# 150110_AriloTX_REV2_3_0_868MHZ_CORRECT_T.net
KiCad netlist of a schematic drawn in EAGLE
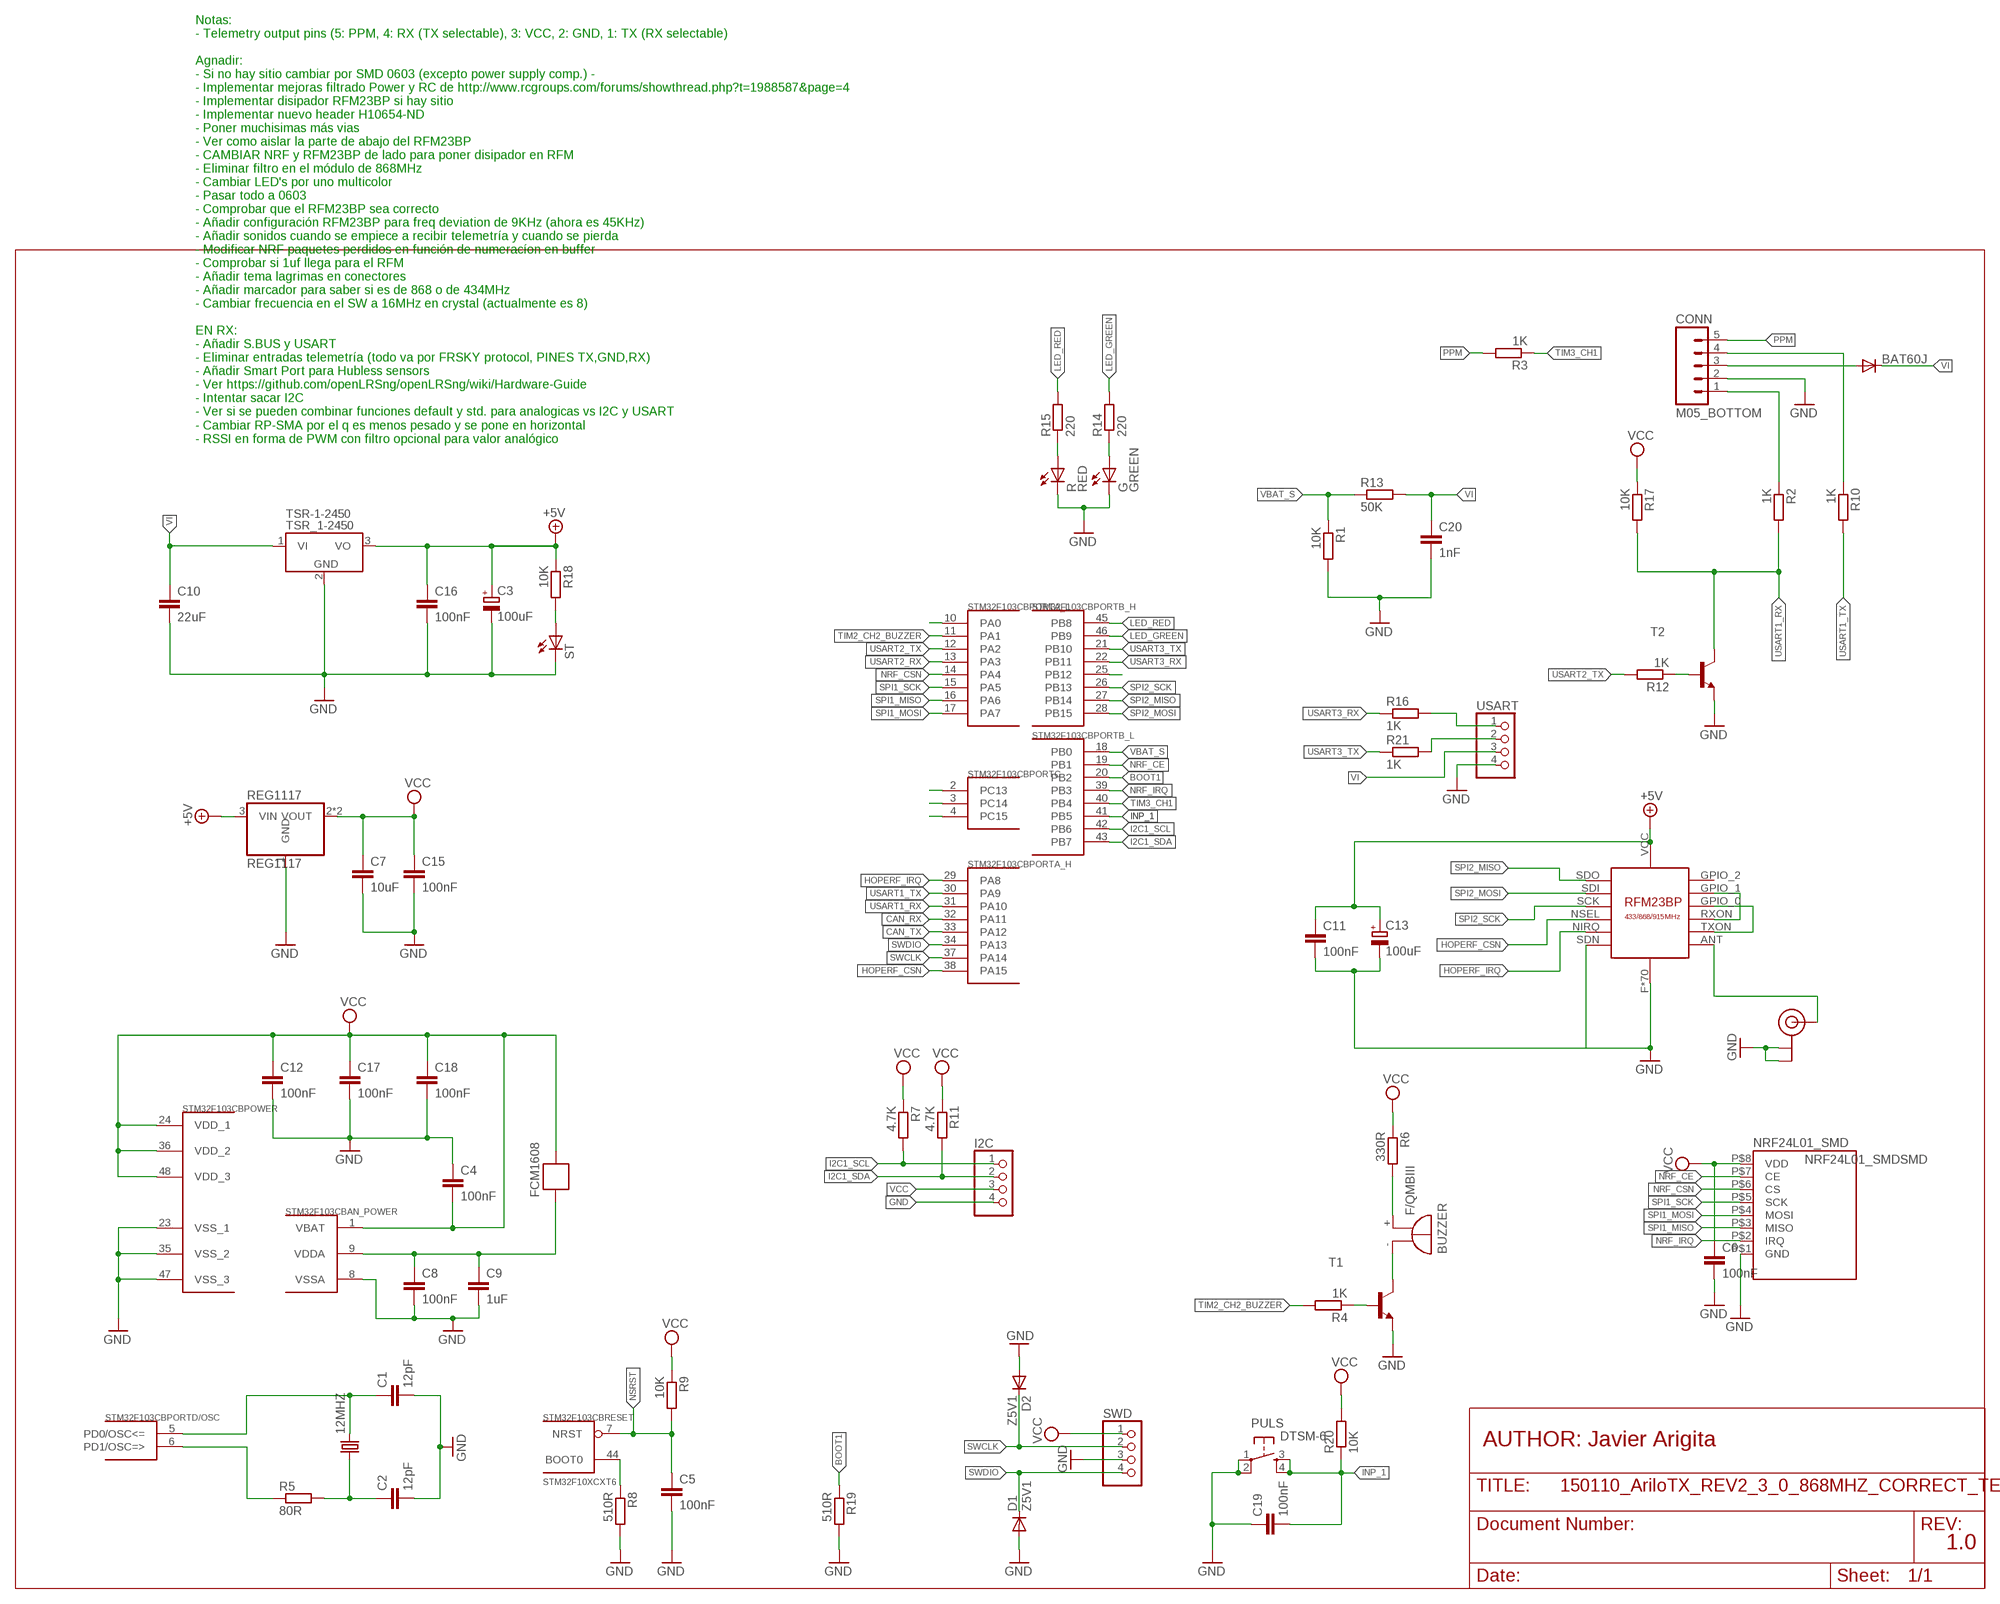
[diagram p0: schematic, sheet 1]

(export (version "E")
  (design (tool "Eeschema 10.0.6"))
  (components
    (comp (ref "12MHZ")
      (value "CRYSTAL5X3")
      (footprint "eagle-import:CRYSTAL-SMD-5X3")
      (libsource (lib "eagle-import") (part "CRYSTAL5X3"))
    )
    (comp (ref "BAT60J")
      (value "DIODE-SOD323-R")
      (footprint "eagle-import:SOD323-R")
      (libsource (lib "eagle-import") (part "DIODE-SOD323-R"))
    )
    (comp (ref "BUZZER")
      (value "F/QMBIII")
      (footprint "eagle-import:F_QMBIII")
      (libsource (lib "eagle-import") (part "F/QMBIII"))
    )
    (comp (ref "C1")
      (value "12pF")
      (footprint "eagle-import:C0603")
      (libsource (lib "eagle-import") (part "C-EUC0603"))
    )
    (comp (ref "C2")
      (value "12pF")
      (footprint "eagle-import:C0603")
      (libsource (lib "eagle-import") (part "C-EUC0603"))
    )
    (comp (ref "C3")
      (value "100uF")
      (footprint "eagle-import:SMC_B")
      (libsource (lib "eagle-import") (part "CPOL-EUSMCB"))
    )
    (comp (ref "C4")
      (value "100nF")
      (footprint "eagle-import:C0603")
      (libsource (lib "eagle-import") (part "C-EUC0603"))
    )
    (comp (ref "C5")
      (value "100nF")
      (footprint "eagle-import:C0603")
      (libsource (lib "eagle-import") (part "C-EUC0603"))
    )
    (comp (ref "C6")
      (value "100nF")
      (footprint "eagle-import:C0603")
      (libsource (lib "eagle-import") (part "C-EUC0603"))
    )
    (comp (ref "C7")
      (value "10uF")
      (footprint "eagle-import:C0805")
      (libsource (lib "eagle-import") (part "C-EUC0805"))
    )
    (comp (ref "C8")
      (value "100nF")
      (footprint "eagle-import:C0603")
      (libsource (lib "eagle-import") (part "C-EUC0603"))
    )
    (comp (ref "C9")
      (value "1uF")
      (footprint "eagle-import:C0603")
      (libsource (lib "eagle-import") (part "C-EUC0603"))
    )
    (comp (ref "C10")
      (value "22uF")
      (footprint "eagle-import:C3216")
      (libsource (lib "eagle-import") (part "resistor_C-EUC3216"))
    )
    (comp (ref "C11")
      (value "100nF")
      (footprint "eagle-import:C0603")
      (libsource (lib "eagle-import") (part "C-EUC0603"))
    )
    (comp (ref "C12")
      (value "100nF")
      (footprint "eagle-import:C0603")
      (libsource (lib "eagle-import") (part "C-EUC0603"))
    )
    (comp (ref "C13")
      (value "100uF")
      (footprint "eagle-import:SMC_B")
      (libsource (lib "eagle-import") (part "CPOL-EUSMCB"))
    )
    (comp (ref "C15")
      (value "100nF")
      (footprint "eagle-import:C0603")
      (libsource (lib "eagle-import") (part "C-EUC0603"))
    )
    (comp (ref "C16")
      (value "100nF")
      (footprint "eagle-import:C0603")
      (libsource (lib "eagle-import") (part "C-EUC0603"))
    )
    (comp (ref "C17")
      (value "100nF")
      (footprint "eagle-import:C0603")
      (libsource (lib "eagle-import") (part "C-EUC0603"))
    )
    (comp (ref "C18")
      (value "100nF")
      (footprint "eagle-import:C0603")
      (libsource (lib "eagle-import") (part "C-EUC0603"))
    )
    (comp (ref "C19")
      (value "100nF")
      (footprint "eagle-import:C0603")
      (libsource (lib "eagle-import") (part "C-EUC0603"))
    )
    (comp (ref "C20")
      (value "1nF")
      (footprint "eagle-import:C0603")
      (libsource (lib "eagle-import") (part "C-EUC0603"))
    )
    (comp (ref "CONN")
      (value "M05_BOTTOM")
      (footprint "eagle-import:M05_BOTTOM")
      (libsource (lib "eagle-import") (part "M05_BOTTOM"))
    )
    (comp (ref "D1")
      (value "Z5V1")
      (footprint "eagle-import:SOD323-R")
      (libsource (lib "eagle-import") (part "DIODE-SOD323-R"))
    )
    (comp (ref "D2")
      (value "Z5V1")
      (footprint "eagle-import:SOD323-R")
      (libsource (lib "eagle-import") (part "DIODE-SOD323-R"))
    )
    (comp (ref "FCM1608")
      (value "FERRITE-BEAD")
      (footprint "eagle-import:R0603")
      (libsource (lib "eagle-import") (part "FERRITE-BEAD"))
    )
    (comp (ref "G")
      (value "GREEN")
      (footprint "eagle-import:CHIP-LED0603")
      (libsource (lib "eagle-import") (part "LEDCHIP-LED0603"))
    )
    (comp (ref "I2C")
      (value "PINHD-1X4")
      (footprint "eagle-import:1X04")
      (libsource (lib "eagle-import") (part "PINHD-1X4"))
    )
    (comp (ref "NRF24L01_SMD")
      (value "NRF24L01_SMDSMD")
      (footprint "eagle-import:NRF24L01_SMD")
      (libsource (lib "eagle-import") (part "NRF24L01_SMDSMD"))
    )
    (comp (ref "PULS")
      (value "DTSM-6")
      (footprint "eagle-import:DTSM-6")
      (libsource (lib "eagle-import") (part "DTSM-6"))
    )
    (comp (ref "R")
      (value "RED")
      (footprint "eagle-import:CHIP-LED0603")
      (libsource (lib "eagle-import") (part "LEDCHIP-LED0603"))
    )
    (comp (ref "R1")
      (value "10K")
      (footprint "eagle-import:R0603")
      (libsource (lib "eagle-import") (part "R-EU_R0603"))
    )
    (comp (ref "R2")
      (value "1K")
      (footprint "eagle-import:R0603")
      (libsource (lib "eagle-import") (part "R-EU_R0603"))
    )
    (comp (ref "R3")
      (value "1K")
      (footprint "eagle-import:R0603")
      (libsource (lib "eagle-import") (part "R-EU_R0603"))
    )
    (comp (ref "R4")
      (value "1K")
      (footprint "eagle-import:R0603")
      (libsource (lib "eagle-import") (part "R-EU_R0603"))
    )
    (comp (ref "R5")
      (value "80R")
      (footprint "eagle-import:R0603")
      (libsource (lib "eagle-import") (part "R-EU_R0603"))
    )
    (comp (ref "R6")
      (value "330R")
      (footprint "eagle-import:R0603")
      (libsource (lib "eagle-import") (part "R-EU_R0603"))
    )
    (comp (ref "R7")
      (value "4.7K")
      (footprint "eagle-import:R0603")
      (libsource (lib "eagle-import") (part "R-EU_R0603"))
    )
    (comp (ref "R8")
      (value "510R")
      (footprint "eagle-import:R0603")
      (libsource (lib "eagle-import") (part "R-EU_R0603"))
    )
    (comp (ref "R9")
      (value "10K")
      (footprint "eagle-import:R0603")
      (libsource (lib "eagle-import") (part "R-EU_R0603"))
    )
    (comp (ref "R10")
      (value "1K")
      (footprint "eagle-import:R0603")
      (libsource (lib "eagle-import") (part "R-EU_R0603"))
    )
    (comp (ref "R11")
      (value "4.7K")
      (footprint "eagle-import:R0603")
      (libsource (lib "eagle-import") (part "R-EU_R0603"))
    )
    (comp (ref "R12")
      (value "1K")
      (footprint "eagle-import:R0603")
      (libsource (lib "eagle-import") (part "R-EU_R0603"))
    )
    (comp (ref "R13")
      (value "50K")
      (footprint "eagle-import:R0603")
      (libsource (lib "eagle-import") (part "R-EU_R0603"))
    )
    (comp (ref "R14")
      (value "220")
      (footprint "eagle-import:R0603")
      (libsource (lib "eagle-import") (part "R-EU_R0603"))
    )
    (comp (ref "R15")
      (value "220")
      (footprint "eagle-import:R0603")
      (libsource (lib "eagle-import") (part "R-EU_R0603"))
    )
    (comp (ref "R16")
      (value "1K")
      (footprint "eagle-import:R0603")
      (libsource (lib "eagle-import") (part "R-EU_R0603"))
    )
    (comp (ref "R17")
      (value "10K")
      (footprint "eagle-import:R0603")
      (libsource (lib "eagle-import") (part "R-EU_R0603"))
    )
    (comp (ref "R18")
      (value "10K")
      (footprint "eagle-import:R0603")
      (libsource (lib "eagle-import") (part "R-EU_R0603"))
    )
    (comp (ref "R19")
      (value "510R")
      (footprint "eagle-import:R0603")
      (libsource (lib "eagle-import") (part "R-EU_R0603"))
    )
    (comp (ref "R20")
      (value "10K")
      (footprint "eagle-import:R0603")
      (libsource (lib "eagle-import") (part "R-EU_R0603"))
    )
    (comp (ref "R21")
      (value "1K")
      (footprint "eagle-import:R0603")
      (libsource (lib "eagle-import") (part "R-EU_R0603"))
    )
    (comp (ref "REG1117")
      (value "REG1117")
      (footprint "eagle-import:SOT223")
      (libsource (lib "eagle-import") (part "REG1117"))
    )
    (comp (ref "ST")
      (value "LEDCHIP-LED0603")
      (footprint "eagle-import:CHIP-LED0603")
      (libsource (lib "eagle-import") (part "LEDCHIP-LED0603"))
    )
    (comp (ref "STM32F103CB")
      (value "STM32F10XCXT6")
      (footprint "eagle-import:TQFP48")
      (libsource (lib "eagle-import") (part "STM32F10XCXT6"))
    )
    (comp (ref "SWD")
      (value "PINHD-1X4")
      (footprint "eagle-import:1X04")
      (libsource (lib "eagle-import") (part "PINHD-1X4"))
    )
    (comp (ref "T1")
      (value "BC848-NPN-SOT23-BEC")
      (footprint "eagle-import:SOT23-BEC")
      (libsource (lib "eagle-import") (part "-NPN-SOT23-BECBC848"))
    )
    (comp (ref "T2")
      (value "BC848-NPN-SOT23-BEC")
      (footprint "eagle-import:SOT23-BEC")
      (libsource (lib "eagle-import") (part "-NPN-SOT23-BECBC848"))
    )
    (comp (ref "TSR-1-2450")
      (value "TSR_1-2450")
      (footprint "eagle-import:TSR-1")
      (libsource (lib "eagle-import") (part "TSR_1-2450"))
    )
    (comp (ref "U$1")
      (value "RFM23BP")
      (footprint "eagle-import:RFM23BP")
      (libsource (lib "eagle-import") (part "RFM23BP"))
    )
    (comp (ref "U.FL")
      (value "U.FL")
      (footprint "eagle-import:U.FL")
      (libsource (lib "eagle-import") (part "U.FL"))
    )
    (comp (ref "USART")
      (value "PINHD-1X4")
      (footprint "eagle-import:1X04")
      (libsource (lib "eagle-import") (part "PINHD-1X4"))
    )
  )
  (nets
    (net (code "1") (name "+5V") (class "Default")
      (node (ref "C11") (pin "1") (pinfunction "1_1") (pintype "passive"))
      (node (ref "C13") (pin "+") (pinfunction "+_+") (pintype "passive"))
      (node (ref "C16") (pin "1") (pinfunction "1_1") (pintype "passive"))
      (node (ref "C3") (pin "+") (pinfunction "+_+") (pintype "passive"))
      (node (ref "R18") (pin "1") (pinfunction "1_1") (pintype "passive"))
      (node (ref "REG1117") (pin "3") (pinfunction "VIN_3") (pintype "input"))
      (node (ref "TSR-1-2450") (pin "3") (pinfunction "VO_3") (pintype "power_in"))
      (node (ref "U$1") (pin "VCC") (pinfunction "VCC_VCC") (pintype "power_in"))
    )
    (net (code "2") (name "BOOT1") (class "Default")
      (node (ref "R19") (pin "1") (pinfunction "1_1") (pintype "passive"))
      (node (ref "STM32F103CB") (pin "20") (pinfunction "PB2_20") (pintype "bidirectional"))
    )
    (net (code "3") (name "CAN_RX") (class "Default")
      (node (ref "STM32F103CB") (pin "32") (pinfunction "PA11_32") (pintype "bidirectional"))
    )
    (net (code "4") (name "CAN_TX") (class "Default")
      (node (ref "STM32F103CB") (pin "33") (pinfunction "PA12_33") (pintype "bidirectional"))
    )
    (net (code "5") (name "GND") (class "Default")
      (node (ref "C1") (pin "2") (pinfunction "2_2") (pintype "passive"))
      (node (ref "C10") (pin "2") (pinfunction "2_2") (pintype "passive"))
      (node (ref "C11") (pin "2") (pinfunction "2_2") (pintype "passive"))
      (node (ref "C12") (pin "2") (pinfunction "2_2") (pintype "passive"))
      (node (ref "C13") (pin "-") (pinfunction "-_-") (pintype "passive"))
      (node (ref "C15") (pin "2") (pinfunction "2_2") (pintype "passive"))
      (node (ref "C16") (pin "2") (pinfunction "2_2") (pintype "passive"))
      (node (ref "C17") (pin "2") (pinfunction "2_2") (pintype "passive"))
      (node (ref "C18") (pin "2") (pinfunction "2_2") (pintype "passive"))
      (node (ref "C19") (pin "1") (pinfunction "1_1") (pintype "passive"))
      (node (ref "C2") (pin "2") (pinfunction "2_2") (pintype "passive"))
      (node (ref "C20") (pin "2") (pinfunction "2_2") (pintype "passive"))
      (node (ref "C3") (pin "-") (pinfunction "-_-") (pintype "passive"))
      (node (ref "C4") (pin "1") (pinfunction "1_1") (pintype "passive"))
      (node (ref "C5") (pin "2") (pinfunction "2_2") (pintype "passive"))
      (node (ref "C6") (pin "2") (pinfunction "2_2") (pintype "passive"))
      (node (ref "C7") (pin "2") (pinfunction "2_2") (pintype "passive"))
      (node (ref "C8") (pin "2") (pinfunction "2_2") (pintype "passive"))
      (node (ref "C9") (pin "2") (pinfunction "2_2") (pintype "passive"))
      (node (ref "CONN") (pin "2") (pinfunction "2_2") (pintype "passive"))
      (node (ref "D1") (pin "A") (pinfunction "A_A") (pintype "passive"))
      (node (ref "D2") (pin "A") (pinfunction "A_A") (pintype "passive"))
      (node (ref "G") (pin "C") (pinfunction "C_C") (pintype "passive"))
      (node (ref "I2C") (pin "4") (pinfunction "4_4") (pintype "passive"))
      (node (ref "NRF24L01_SMD") (pin "P$1") (pinfunction "GND_P$1") (pintype "power_in"))
      (node (ref "PULS") (pin "1") (pinfunction "1_1") (pintype "passive"))
      (node (ref "PULS") (pin "2") (pinfunction "2_2") (pintype "passive"))
      (node (ref "R") (pin "C") (pinfunction "C_C") (pintype "passive"))
      (node (ref "R1") (pin "2") (pinfunction "2_2") (pintype "passive"))
      (node (ref "R19") (pin "2") (pinfunction "2_2") (pintype "passive"))
      (node (ref "R8") (pin "2") (pinfunction "2_2") (pintype "passive"))
      (node (ref "REG1117") (pin "1") (pinfunction "GND_1") (pintype "power_in"))
      (node (ref "ST") (pin "C") (pinfunction "C_C") (pintype "passive"))
      (node (ref "STM32F103CB") (pin "23") (pinfunction "VSS_1_23") (pintype "power_in"))
      (node (ref "STM32F103CB") (pin "35") (pinfunction "VSS_2_35") (pintype "power_in"))
      (node (ref "STM32F103CB") (pin "47") (pinfunction "VSS_3_47") (pintype "power_in"))
      (node (ref "STM32F103CB") (pin "8") (pinfunction "VSSA_8") (pintype "power_in"))
      (node (ref "SWD") (pin "3") (pinfunction "3_3") (pintype "passive"))
      (node (ref "T1") (pin "E") (pinfunction "E_E") (pintype "passive"))
      (node (ref "T2") (pin "E") (pinfunction "E_E") (pintype "passive"))
      (node (ref "TSR-1-2450") (pin "2") (pinfunction "GND_2") (pintype "power_in"))
      (node (ref "U$1") (pin "F") (pinfunction "GND_F") (pintype "power_in"))
      (node (ref "U$1") (pin "F1") (pinfunction "GND_F1") (pintype "power_in"))
      (node (ref "U$1") (pin "F10") (pinfunction "GND_F10") (pintype "power_in"))
      (node (ref "U$1") (pin "F11") (pinfunction "GND_F11") (pintype "power_in"))
      (node (ref "U$1") (pin "F12") (pinfunction "GND_F12") (pintype "power_in"))
      (node (ref "U$1") (pin "F13") (pinfunction "GND_F13") (pintype "power_in"))
      (node (ref "U$1") (pin "F14") (pinfunction "GND_F14") (pintype "power_in"))
      (node (ref "U$1") (pin "F15") (pinfunction "GND_F15") (pintype "power_in"))
      (node (ref "U$1") (pin "F16") (pinfunction "GND_F16") (pintype "power_in"))
      (node (ref "U$1") (pin "F17") (pinfunction "GND_F17") (pintype "power_in"))
      (node (ref "U$1") (pin "F18") (pinfunction "GND_F18") (pintype "power_in"))
      (node (ref "U$1") (pin "F19") (pinfunction "GND_F19") (pintype "power_in"))
      (node (ref "U$1") (pin "F2") (pinfunction "GND_F2") (pintype "power_in"))
      (node (ref "U$1") (pin "F20") (pinfunction "GND_F20") (pintype "power_in"))
      (node (ref "U$1") (pin "F21") (pinfunction "GND_F21") (pintype "power_in"))
      (node (ref "U$1") (pin "F22") (pinfunction "GND_F22") (pintype "power_in"))
      (node (ref "U$1") (pin "F23") (pinfunction "GND_F23") (pintype "power_in"))
      (node (ref "U$1") (pin "F24") (pinfunction "GND_F24") (pintype "power_in"))
      (node (ref "U$1") (pin "F25") (pinfunction "GND_F25") (pintype "power_in"))
      (node (ref "U$1") (pin "F26") (pinfunction "GND_F26") (pintype "power_in"))
      (node (ref "U$1") (pin "F27") (pinfunction "GND_F27") (pintype "power_in"))
      (node (ref "U$1") (pin "F28") (pinfunction "GND_F28") (pintype "power_in"))
      (node (ref "U$1") (pin "F29") (pinfunction "GND_F29") (pintype "power_in"))
      (node (ref "U$1") (pin "F3") (pinfunction "GND_F3") (pintype "power_in"))
      (node (ref "U$1") (pin "F30") (pinfunction "GND_F30") (pintype "power_in"))
      (node (ref "U$1") (pin "F31") (pinfunction "GND_F31") (pintype "power_in"))
      (node (ref "U$1") (pin "F32") (pinfunction "GND_F32") (pintype "power_in"))
      (node (ref "U$1") (pin "F33") (pinfunction "GND_F33") (pintype "power_in"))
      (node (ref "U$1") (pin "F34") (pinfunction "GND_F34") (pintype "power_in"))
      (node (ref "U$1") (pin "F35") (pinfunction "GND_F35") (pintype "power_in"))
      (node (ref "U$1") (pin "F36") (pinfunction "GND_F36") (pintype "power_in"))
      (node (ref "U$1") (pin "F37") (pinfunction "GND_F37") (pintype "power_in"))
      (node (ref "U$1") (pin "F38") (pinfunction "GND_F38") (pintype "power_in"))
      (node (ref "U$1") (pin "F39") (pinfunction "GND_F39") (pintype "power_in"))
      (node (ref "U$1") (pin "F4") (pinfunction "GND_F4") (pintype "power_in"))
      (node (ref "U$1") (pin "F40") (pinfunction "GND_F40") (pintype "power_in"))
      (node (ref "U$1") (pin "F41") (pinfunction "GND_F41") (pintype "power_in"))
      (node (ref "U$1") (pin "F42") (pinfunction "GND_F42") (pintype "power_in"))
      (node (ref "U$1") (pin "F43") (pinfunction "GND_F43") (pintype "power_in"))
      (node (ref "U$1") (pin "F44") (pinfunction "GND_F44") (pintype "power_in"))
      (node (ref "U$1") (pin "F45") (pinfunction "GND_F45") (pintype "power_in"))
      (node (ref "U$1") (pin "F46") (pinfunction "GND_F46") (pintype "power_in"))
      (node (ref "U$1") (pin "F47") (pinfunction "GND_F47") (pintype "power_in"))
      (node (ref "U$1") (pin "F48") (pinfunction "GND_F48") (pintype "power_in"))
      (node (ref "U$1") (pin "F49") (pinfunction "GND_F49") (pintype "power_in"))
      (node (ref "U$1") (pin "F5") (pinfunction "GND_F5") (pintype "power_in"))
      (node (ref "U$1") (pin "F50") (pinfunction "GND_F50") (pintype "power_in"))
      (node (ref "U$1") (pin "F51") (pinfunction "GND_F51") (pintype "power_in"))
      (node (ref "U$1") (pin "F52") (pinfunction "GND_F52") (pintype "power_in"))
      (node (ref "U$1") (pin "F53") (pinfunction "GND_F53") (pintype "power_in"))
      (node (ref "U$1") (pin "F54") (pinfunction "GND_F54") (pintype "power_in"))
      (node (ref "U$1") (pin "F55") (pinfunction "GND_F55") (pintype "power_in"))
      (node (ref "U$1") (pin "F56") (pinfunction "GND_F56") (pintype "power_in"))
      (node (ref "U$1") (pin "F57") (pinfunction "GND_F57") (pintype "power_in"))
      (node (ref "U$1") (pin "F58") (pinfunction "GND_F58") (pintype "power_in"))
      (node (ref "U$1") (pin "F59") (pinfunction "GND_F59") (pintype "power_in"))
      (node (ref "U$1") (pin "F6") (pinfunction "GND_F6") (pintype "power_in"))
      (node (ref "U$1") (pin "F60") (pinfunction "GND_F60") (pintype "power_in"))
      (node (ref "U$1") (pin "F61") (pinfunction "GND_F61") (pintype "power_in"))
      (node (ref "U$1") (pin "F62") (pinfunction "GND_F62") (pintype "power_in"))
      (node (ref "U$1") (pin "F63") (pinfunction "GND_F63") (pintype "power_in"))
      (node (ref "U$1") (pin "F64") (pinfunction "GND_F64") (pintype "power_in"))
      (node (ref "U$1") (pin "F65") (pinfunction "GND_F65") (pintype "power_in"))
      (node (ref "U$1") (pin "F7") (pinfunction "GND_F7") (pintype "power_in"))
      (node (ref "U$1") (pin "F8") (pinfunction "GND_F8") (pintype "power_in"))
      (node (ref "U$1") (pin "F9") (pinfunction "GND_F9") (pintype "power_in"))
      (node (ref "U$1") (pin "GND1") (pinfunction "GND_GND1") (pintype "power_in"))
      (node (ref "U$1") (pin "GND2") (pinfunction "GND_GND2") (pintype "power_in"))
      (node (ref "U$1") (pin "GND3") (pinfunction "GND_GND3") (pintype "power_in"))
      (node (ref "U$1") (pin "GND_HEAT") (pinfunction "GND_GND_HEAT") (pintype "power_in"))
      (node (ref "U$1") (pin "SDN") (pinfunction "SDN_SDN") (pintype "bidirectional"))
      (node (ref "U.FL") (pin "P$1") (pinfunction "GND_P$1") (pintype "bidirectional"))
      (node (ref "U.FL") (pin "P$2") (pinfunction "GND_P$2") (pintype "bidirectional"))
      (node (ref "USART") (pin "4") (pinfunction "4_4") (pintype "passive"))
    )
    (net (code "6") (name "HOPERF_CSN") (class "Default")
      (node (ref "STM32F103CB") (pin "38") (pinfunction "PA15_38") (pintype "bidirectional"))
      (node (ref "U$1") (pin "NSEL") (pinfunction "NSEL_NSEL") (pintype "bidirectional"))
    )
    (net (code "7") (name "HOPERF_IRQ") (class "Default")
      (node (ref "STM32F103CB") (pin "29") (pinfunction "PA8_29") (pintype "bidirectional"))
      (node (ref "U$1") (pin "NIRQ") (pinfunction "NIRQ_NIRQ") (pintype "bidirectional"))
    )
    (net (code "8") (name "I2C1_SCL") (class "Default")
      (node (ref "I2C") (pin "1") (pinfunction "1_1") (pintype "passive"))
      (node (ref "R7") (pin "2") (pinfunction "2_2") (pintype "passive"))
      (node (ref "STM32F103CB") (pin "42") (pinfunction "PB6_42") (pintype "bidirectional"))
    )
    (net (code "9") (name "I2C1_SDA") (class "Default")
      (node (ref "I2C") (pin "2") (pinfunction "2_2") (pintype "passive"))
      (node (ref "R11") (pin "2") (pinfunction "2_2") (pintype "passive"))
      (node (ref "STM32F103CB") (pin "43") (pinfunction "PB7_43") (pintype "bidirectional"))
    )
    (net (code "10") (name "INP_1") (class "Default")
      (node (ref "C19") (pin "2") (pinfunction "2_2") (pintype "passive"))
      (node (ref "PULS") (pin "3") (pinfunction "3_3") (pintype "passive"))
      (node (ref "PULS") (pin "4") (pinfunction "4_4") (pintype "passive"))
      (node (ref "R20") (pin "1") (pinfunction "1_1") (pintype "passive"))
      (node (ref "STM32F103CB") (pin "41") (pinfunction "PB5_41") (pintype "bidirectional"))
    )
    (net (code "11") (name "LED_GREEN") (class "Default")
      (node (ref "R14") (pin "2") (pinfunction "2_2") (pintype "passive"))
      (node (ref "STM32F103CB") (pin "46") (pinfunction "PB9_46") (pintype "bidirectional"))
    )
    (net (code "12") (name "LED_RED") (class "Default")
      (node (ref "R15") (pin "2") (pinfunction "2_2") (pintype "passive"))
      (node (ref "STM32F103CB") (pin "45") (pinfunction "PB8_45") (pintype "bidirectional"))
    )
    (net (code "13") (name "NRF_CE") (class "Default")
      (node (ref "NRF24L01_SMD") (pin "P$7") (pinfunction "CE_P$7") (pintype "input"))
      (node (ref "STM32F103CB") (pin "19") (pinfunction "PB1_19") (pintype "bidirectional"))
    )
    (net (code "14") (name "NRF_CSN") (class "Default")
      (node (ref "NRF24L01_SMD") (pin "P$6") (pinfunction "CS_P$6") (pintype "input"))
      (node (ref "STM32F103CB") (pin "14") (pinfunction "PA4_14") (pintype "bidirectional"))
    )
    (net (code "15") (name "NRF_IRQ") (class "Default")
      (node (ref "NRF24L01_SMD") (pin "P$2") (pinfunction "IRQ_P$2") (pintype "output"))
      (node (ref "STM32F103CB") (pin "39") (pinfunction "PB3_39") (pintype "bidirectional"))
    )
    (net (code "16") (name "NSRST") (class "Default")
      (node (ref "C5") (pin "1") (pinfunction "1_1") (pintype "passive"))
      (node (ref "R9") (pin "2") (pinfunction "2_2") (pintype "passive"))
      (node (ref "STM32F103CB") (pin "7") (pinfunction "NRST_7") (pintype "input"))
    )
    (net (code "17") (name "Net-(12MHZ-2)") (class "Default")
      (node (ref "12MHZ") (pin "3") (pinfunction "2_3") (pintype "passive"))
      (node (ref "C1") (pin "1") (pinfunction "1_1") (pintype "passive"))
      (node (ref "STM32F103CB") (pin "5") (pinfunction "PD0/OSC<=_5") (pintype "bidirectional"))
    )
    (net (code "18") (name "Net-(12MHZ-Pad1)") (class "Default")
      (node (ref "12MHZ") (pin "1") (pinfunction "1_1") (pintype "passive"))
      (node (ref "C2") (pin "1") (pinfunction "1_1") (pintype "passive"))
      (node (ref "R5") (pin "2") (pinfunction "2_2") (pintype "passive"))
    )
    (net (code "19") (name "Net-(BAT60J-PadA)") (class "Default")
      (node (ref "BAT60J") (pin "A") (pinfunction "A_A") (pintype "passive"))
      (node (ref "CONN") (pin "3") (pinfunction "3_3") (pintype "passive"))
    )
    (net (code "20") (name "Net-(BUZZER-+)") (class "Default")
      (node (ref "BUZZER") (pin "-") (pinfunction "+_-") (pintype "passive"))
      (node (ref "T1") (pin "C") (pinfunction "C_C") (pintype "passive"))
    )
    (net (code "21") (name "Net-(BUZZER--)") (class "Default")
      (node (ref "BUZZER") (pin "+") (pinfunction "-_+") (pintype "passive"))
      (node (ref "R6") (pin "2") (pinfunction "2_2") (pintype "passive"))
    )
    (net (code "22") (name "Net-(CONN-Pad1)") (class "Default")
      (node (ref "CONN") (pin "1") (pinfunction "1_1") (pintype "passive"))
      (node (ref "R2") (pin "1") (pinfunction "1_1") (pintype "passive"))
    )
    (net (code "23") (name "Net-(CONN-Pad4)") (class "Default")
      (node (ref "CONN") (pin "4") (pinfunction "4_4") (pintype "passive"))
      (node (ref "R10") (pin "1") (pinfunction "1_1") (pintype "passive"))
    )
    (net (code "24") (name "Net-(FCM1608-P$2)") (class "Default")
      (node (ref "C8") (pin "1") (pinfunction "1_1") (pintype "passive"))
      (node (ref "C9") (pin "1") (pinfunction "1_1") (pintype "passive"))
      (node (ref "FCM1608") (pin "2") (pinfunction "P$2_2") (pintype "bidirectional"))
      (node (ref "STM32F103CB") (pin "9") (pinfunction "VDDA_9") (pintype "power_in"))
    )
    (net (code "25") (name "Net-(G-PadA)") (class "Default")
      (node (ref "G") (pin "A") (pinfunction "A_A") (pintype "passive"))
      (node (ref "R14") (pin "1") (pinfunction "1_1") (pintype "passive"))
    )
    (net (code "26") (name "Net-(R-PadA)") (class "Default")
      (node (ref "R") (pin "A") (pinfunction "A_A") (pintype "passive"))
      (node (ref "R15") (pin "1") (pinfunction "1_1") (pintype "passive"))
    )
    (net (code "27") (name "Net-(R4-Pad1)") (class "Default")
      (node (ref "R4") (pin "1") (pinfunction "1_1") (pintype "passive"))
      (node (ref "T1") (pin "B") (pinfunction "B_B") (pintype "passive"))
    )
    (net (code "28") (name "Net-(R12-Pad1)") (class "Default")
      (node (ref "R12") (pin "1") (pinfunction "1_1") (pintype "passive"))
      (node (ref "T2") (pin "B") (pinfunction "B_B") (pintype "passive"))
    )
    (net (code "29") (name "Net-(R16-Pad2)") (class "Default")
      (node (ref "R16") (pin "2") (pinfunction "2_2") (pintype "passive"))
      (node (ref "USART") (pin "1") (pinfunction "1_1") (pintype "passive"))
    )
    (net (code "30") (name "Net-(R18-Pad2)") (class "Default")
      (node (ref "R18") (pin "2") (pinfunction "2_2") (pintype "passive"))
      (node (ref "ST") (pin "A") (pinfunction "A_A") (pintype "passive"))
    )
    (net (code "31") (name "Net-(R21-Pad2)") (class "Default")
      (node (ref "R21") (pin "2") (pinfunction "2_2") (pintype "passive"))
      (node (ref "USART") (pin "2") (pinfunction "2_2") (pintype "passive"))
    )
    (net (code "32") (name "Net-(STM32F103CBG-PD1{slash}OSC=>)") (class "Default")
      (node (ref "R5") (pin "1") (pinfunction "1_1") (pintype "passive"))
      (node (ref "STM32F103CB") (pin "6") (pinfunction "PD1/OSC=>_6") (pintype "bidirectional"))
    )
    (net (code "33") (name "Net-(STM32F103CBI-BOOT0)") (class "Default")
      (node (ref "R8") (pin "1") (pinfunction "1_1") (pintype "passive"))
      (node (ref "STM32F103CB") (pin "44") (pinfunction "BOOT0_44") (pintype "input"))
    )
    (net (code "34") (name "Net-(U$1-PadGPIO_0)") (class "Default")
      (node (ref "U$1") (pin "GPIO_0") (pinfunction "GPIO_0_GPIO_0") (pintype "bidirectional"))
      (node (ref "U$1") (pin "TXON") (pinfunction "TXON_TXON") (pintype "bidirectional"))
    )
    (net (code "35") (name "Net-(U$1-PadGPIO_1)") (class "Default")
      (node (ref "U$1") (pin "GPIO_1") (pinfunction "GPIO_1_GPIO_1") (pintype "bidirectional"))
      (node (ref "U$1") (pin "RXON") (pinfunction "RXON_RXON") (pintype "bidirectional"))
    )
    (net (code "36") (name "Net-(U.FL-SIGNAL)") (class "Default")
      (node (ref "U$1") (pin "ANT") (pinfunction "ANT_ANT") (pintype "bidirectional"))
      (node (ref "U.FL") (pin "P$3") (pinfunction "SIGNAL_P$3") (pintype "bidirectional"))
    )
    (net (code "37") (name "PPM") (class "Default")
      (node (ref "CONN") (pin "5") (pinfunction "5_5") (pintype "passive"))
      (node (ref "R3") (pin "2") (pinfunction "2_2") (pintype "passive"))
    )
    (net (code "38") (name "SPI1_MISO") (class "Default")
      (node (ref "NRF24L01_SMD") (pin "P$3") (pinfunction "MISO_P$3") (pintype "output"))
      (node (ref "STM32F103CB") (pin "16") (pinfunction "PA6_16") (pintype "bidirectional"))
    )
    (net (code "39") (name "SPI1_MOSI") (class "Default")
      (node (ref "NRF24L01_SMD") (pin "P$4") (pinfunction "MOSI_P$4") (pintype "input"))
      (node (ref "STM32F103CB") (pin "17") (pinfunction "PA7_17") (pintype "bidirectional"))
    )
    (net (code "40") (name "SPI1_SCK") (class "Default")
      (node (ref "NRF24L01_SMD") (pin "P$5") (pinfunction "SCK_P$5") (pintype "input"))
      (node (ref "STM32F103CB") (pin "15") (pinfunction "PA5_15") (pintype "bidirectional"))
    )
    (net (code "41") (name "SPI2_MISO") (class "Default")
      (node (ref "STM32F103CB") (pin "27") (pinfunction "PB14_27") (pintype "bidirectional"))
      (node (ref "U$1") (pin "SDO") (pinfunction "SDO_SDO") (pintype "bidirectional"))
    )
    (net (code "42") (name "SPI2_MOSI") (class "Default")
      (node (ref "STM32F103CB") (pin "28") (pinfunction "PB15_28") (pintype "bidirectional"))
      (node (ref "U$1") (pin "SDI") (pinfunction "SDI_SDI") (pintype "bidirectional"))
    )
    (net (code "43") (name "SPI2_SCK") (class "Default")
      (node (ref "STM32F103CB") (pin "26") (pinfunction "PB13_26") (pintype "bidirectional"))
      (node (ref "U$1") (pin "SCK") (pinfunction "SCK_SCK") (pintype "bidirectional"))
    )
    (net (code "44") (name "SWCLK") (class "Default")
      (node (ref "D2") (pin "C") (pinfunction "C_C") (pintype "passive"))
      (node (ref "STM32F103CB") (pin "37") (pinfunction "PA14_37") (pintype "bidirectional"))
      (node (ref "SWD") (pin "2") (pinfunction "2_2") (pintype "passive"))
    )
    (net (code "45") (name "SWDIO") (class "Default")
      (node (ref "D1") (pin "C") (pinfunction "C_C") (pintype "passive"))
      (node (ref "STM32F103CB") (pin "34") (pinfunction "PA13_34") (pintype "bidirectional"))
      (node (ref "SWD") (pin "4") (pinfunction "4_4") (pintype "passive"))
    )
    (net (code "46") (name "TIM2_CH2_BUZZER") (class "Default")
      (node (ref "R4") (pin "2") (pinfunction "2_2") (pintype "passive"))
      (node (ref "STM32F103CB") (pin "11") (pinfunction "PA1_11") (pintype "bidirectional"))
    )
    (net (code "47") (name "TIM3_CH1") (class "Default")
      (node (ref "R3") (pin "1") (pinfunction "1_1") (pintype "passive"))
      (node (ref "STM32F103CB") (pin "40") (pinfunction "PB4_40") (pintype "bidirectional"))
    )
    (net (code "48") (name "USART1_RX") (class "Default")
      (node (ref "R17") (pin "2") (pinfunction "2_2") (pintype "passive"))
      (node (ref "R2") (pin "2") (pinfunction "2_2") (pintype "passive"))
      (node (ref "STM32F103CB") (pin "31") (pinfunction "PA10_31") (pintype "bidirectional"))
      (node (ref "T2") (pin "C") (pinfunction "C_C") (pintype "passive"))
    )
    (net (code "49") (name "USART1_TX") (class "Default")
      (node (ref "R10") (pin "2") (pinfunction "2_2") (pintype "passive"))
      (node (ref "STM32F103CB") (pin "30") (pinfunction "PA9_30") (pintype "bidirectional"))
    )
    (net (code "50") (name "USART2_RX") (class "Default")
      (node (ref "STM32F103CB") (pin "13") (pinfunction "PA3_13") (pintype "bidirectional"))
    )
    (net (code "51") (name "USART2_TX") (class "Default")
      (node (ref "R12") (pin "2") (pinfunction "2_2") (pintype "passive"))
      (node (ref "STM32F103CB") (pin "12") (pinfunction "PA2_12") (pintype "bidirectional"))
    )
    (net (code "52") (name "USART3_RX") (class "Default")
      (node (ref "R16") (pin "1") (pinfunction "1_1") (pintype "passive"))
      (node (ref "STM32F103CB") (pin "22") (pinfunction "PB11_22") (pintype "bidirectional"))
    )
    (net (code "53") (name "USART3_TX") (class "Default")
      (node (ref "R21") (pin "1") (pinfunction "1_1") (pintype "passive"))
      (node (ref "STM32F103CB") (pin "21") (pinfunction "PB10_21") (pintype "bidirectional"))
    )
    (net (code "54") (name "VBAT_S") (class "Default")
      (node (ref "R1") (pin "1") (pinfunction "1_1") (pintype "passive"))
      (node (ref "R13") (pin "1") (pinfunction "1_1") (pintype "passive"))
      (node (ref "STM32F103CB") (pin "18") (pinfunction "PB0_18") (pintype "bidirectional"))
    )
    (net (code "55") (name "VCC") (class "Default")
      (node (ref "C12") (pin "1") (pinfunction "1_1") (pintype "passive"))
      (node (ref "C15") (pin "1") (pinfunction "1_1") (pintype "passive"))
      (node (ref "C17") (pin "1") (pinfunction "1_1") (pintype "passive"))
      (node (ref "C18") (pin "1") (pinfunction "1_1") (pintype "passive"))
      (node (ref "C4") (pin "2") (pinfunction "2_2") (pintype "passive"))
      (node (ref "C6") (pin "1") (pinfunction "1_1") (pintype "passive"))
      (node (ref "C7") (pin "1") (pinfunction "1_1") (pintype "passive"))
      (node (ref "FCM1608") (pin "1") (pinfunction "P$1_1") (pintype "bidirectional"))
      (node (ref "I2C") (pin "3") (pinfunction "3_3") (pintype "passive"))
      (node (ref "NRF24L01_SMD") (pin "P$8") (pinfunction "VDD_P$8") (pintype "bidirectional"))
      (node (ref "R11") (pin "1") (pinfunction "1_1") (pintype "passive"))
      (node (ref "R17") (pin "1") (pinfunction "1_1") (pintype "passive"))
      (node (ref "R20") (pin "2") (pinfunction "2_2") (pintype "passive"))
      (node (ref "R6") (pin "1") (pinfunction "1_1") (pintype "passive"))
      (node (ref "R7") (pin "1") (pinfunction "1_1") (pintype "passive"))
      (node (ref "R9") (pin "1") (pinfunction "1_1") (pintype "passive"))
      (node (ref "REG1117") (pin "2") (pinfunction "VOUT_2") (pintype "power_in"))
      (node (ref "REG1117") (pin "4") (pinfunction "VOUT_4") (pintype "power_in"))
      (node (ref "STM32F103CB") (pin "1") (pinfunction "VBAT_1") (pintype "power_in"))
      (node (ref "STM32F103CB") (pin "24") (pinfunction "VDD_1_24") (pintype "power_in"))
      (node (ref "STM32F103CB") (pin "36") (pinfunction "VDD_2_36") (pintype "power_in"))
      (node (ref "STM32F103CB") (pin "48") (pinfunction "VDD_3_48") (pintype "power_in"))
      (node (ref "SWD") (pin "1") (pinfunction "1_1") (pintype "passive"))
    )
    (net (code "56") (name "VI") (class "Default")
      (node (ref "BAT60J") (pin "C") (pinfunction "C_C") (pintype "passive"))
      (node (ref "C10") (pin "1") (pinfunction "1_1") (pintype "passive"))
      (node (ref "C20") (pin "1") (pinfunction "1_1") (pintype "passive"))
      (node (ref "R13") (pin "2") (pinfunction "2_2") (pintype "passive"))
      (node (ref "TSR-1-2450") (pin "1") (pinfunction "VI_1") (pintype "power_in"))
      (node (ref "USART") (pin "3") (pinfunction "3_3") (pintype "passive"))
    )
    (net (code "57") (name "unconnected-(STM32F103CBC-PA0-Pad10)") (class "Default")
      (node (ref "STM32F103CB") (pin "10") (pinfunction "PA0_10") (pintype "bidirectional"))
    )
    (net (code "58") (name "unconnected-(STM32F103CBD-PB12-Pad25)") (class "Default")
      (node (ref "STM32F103CB") (pin "25") (pinfunction "PB12_25") (pintype "bidirectional"))
    )
    (net (code "59") (name "unconnected-(STM32F103CBF-PC13-Pad2)") (class "Default")
      (node (ref "STM32F103CB") (pin "2") (pinfunction "PC13_2") (pintype "bidirectional"))
    )
    (net (code "60") (name "unconnected-(STM32F103CBF-PC14-Pad3)") (class "Default")
      (node (ref "STM32F103CB") (pin "3") (pinfunction "PC14_3") (pintype "bidirectional"))
    )
    (net (code "61") (name "unconnected-(STM32F103CBF-PC15-Pad4)") (class "Default")
      (node (ref "STM32F103CB") (pin "4") (pinfunction "PC15_4") (pintype "bidirectional"))
    )
    (net (code "62") (name "unconnected-(U$1-PadGPIO_2)") (class "Default")
      (node (ref "U$1") (pin "GPIO_2") (pinfunction "GPIO_2_GPIO_2") (pintype "bidirectional"))
    )
  )
)
